# Temp_converter.net
KiCad netlist of a schematic drawn in Altium Designer
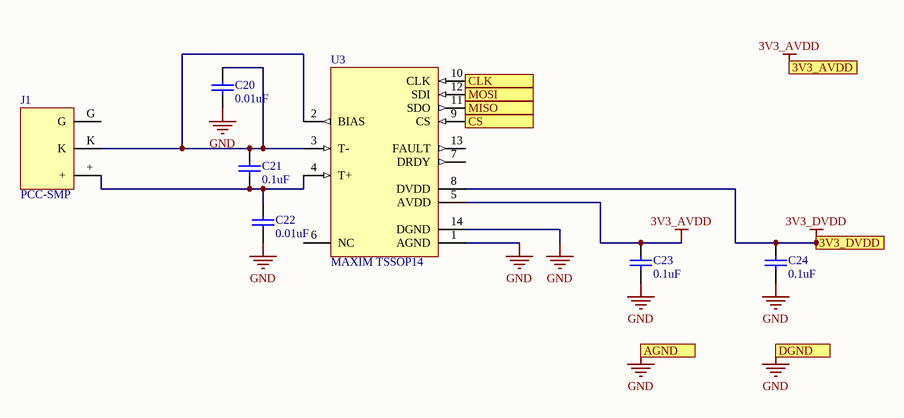
[diagram p0: Temp_converter.SchDoc]

(export (version "E")
  (design (tool "Eeschema 10.0.6"))
  (components
    (comp (ref "C20")
      (value "0.01uF")
      (footprint "C0805")
      (description "0805 Capacitor")
      (libsource (lib "PARSEC") (part "C0805"))
    )
    (comp (ref "C21")
      (value "0.1uF")
      (footprint "C0805")
      (description "0805 Capacitor")
      (libsource (lib "PARSEC") (part "C0805"))
    )
    (comp (ref "C22")
      (value "0.01uF")
      (footprint "C0805")
      (description "0805 Capacitor")
      (libsource (lib "PARSEC") (part "C0805"))
    )
    (comp (ref "C23")
      (value "0.1uF")
      (footprint "C0805")
      (description "0805 Capacitor")
      (libsource (lib "PARSEC") (part "C0805"))
    )
    (comp (ref "C24")
      (value "0.1uF")
      (footprint "C0805")
      (description "0805 Capacitor")
      (libsource (lib "PARSEC") (part "C0805"))
    )
    (comp (ref "J1")
      (value "PCC-SMP")
      (footprint "PCC-SMP")
      (description "THERMOCOUPLE CONNECTOR")
      (libsource (lib "thermocouple_connector") (part "PCC-SMP"))
    )
    (comp (ref "U3")
      (value "MAXIM TSSOP14")
      (footprint "MAXIM TSSOP14")
      (libsource (lib "PARSEC_TC") (part "MAXIM TSSOP14"))
    )
  )
  (nets
    (net (code "1") (name "/CLK") (class "Default")
      (node (ref "U3") (pin "10") (pinfunction "CLK_10") (pintype "input"))
    )
    (net (code "2") (name "/CS") (class "Default")
      (node (ref "U3") (pin "9") (pinfunction "CS_9") (pintype "input"))
    )
    (net (code "3") (name "/MISO") (class "Default")
      (node (ref "U3") (pin "11") (pinfunction "SDO_11") (pintype "output"))
    )
    (net (code "4") (name "/MOSI") (class "Default")
      (node (ref "U3") (pin "12") (pinfunction "SDI_12") (pintype "input"))
    )
    (net (code "5") (name "3V3_AVDD") (class "Default")
      (node (ref "C23") (pin "1") (pinfunction "1_1") (pintype "passive"))
      (node (ref "U3") (pin "5") (pinfunction "AVDD_5") (pintype "power_in"))
    )
    (net (code "6") (name "3V3_DVDD") (class "Default")
      (node (ref "C24") (pin "1") (pinfunction "1_1") (pintype "passive"))
      (node (ref "U3") (pin "8") (pinfunction "DVDD_8") (pintype "power_in"))
    )
    (net (code "7") (name "GND") (class "Default")
      (node (ref "C20") (pin "2") (pinfunction "2_2") (pintype "passive"))
      (node (ref "C22") (pin "2") (pinfunction "2_2") (pintype "passive"))
      (node (ref "C23") (pin "2") (pinfunction "2_2") (pintype "passive"))
      (node (ref "C24") (pin "2") (pinfunction "2_2") (pintype "passive"))
      (node (ref "U3") (pin "1") (pinfunction "AGND_1") (pintype "passive"))
      (node (ref "U3") (pin "14") (pinfunction "DGND_14") (pintype "passive"))
    )
    (net (code "8") (name "Net-(U3-BIAS)") (class "Default")
      (node (ref "C20") (pin "1") (pinfunction "1_1") (pintype "passive"))
      (node (ref "C21") (pin "1") (pinfunction "1_1") (pintype "passive"))
      (node (ref "J1") (pin "K") (pinfunction "K_K") (pintype "passive"))
      (node (ref "U3") (pin "2") (pinfunction "BIAS_2") (pintype "output"))
      (node (ref "U3") (pin "3") (pinfunction "T-_3") (pintype "input"))
    )
    (net (code "9") (name "Net-(U3-T+)") (class "Default")
      (node (ref "C21") (pin "2") (pinfunction "2_2") (pintype "passive"))
      (node (ref "C22") (pin "1") (pinfunction "1_1") (pintype "passive"))
      (node (ref "J1") (pin "+") (pinfunction "+_+") (pintype "passive"))
      (node (ref "U3") (pin "4") (pinfunction "T+_4") (pintype "input"))
    )
    (net (code "10") (name "unconnected-(J1-PadG)") (class "Default")
      (node (ref "J1") (pin "G") (pinfunction "G_G") (pintype "passive"))
    )
    (net (code "11") (name "unconnected-(U3-DRDY-Pad7)") (class "Default")
      (node (ref "U3") (pin "7") (pinfunction "DRDY_7") (pintype "output"))
    )
    (net (code "12") (name "unconnected-(U3-FAULT-Pad13)") (class "Default")
      (node (ref "U3") (pin "13") (pinfunction "FAULT_13") (pintype "output"))
    )
    (net (code "13") (name "unconnected-(U3-NC-Pad6)") (class "Default")
      (node (ref "U3") (pin "6") (pinfunction "NC_6") (pintype "passive"))
    )
  )
)
